# quadruped-robot.net
KiCad netlist of a schematic drawn in EAGLE
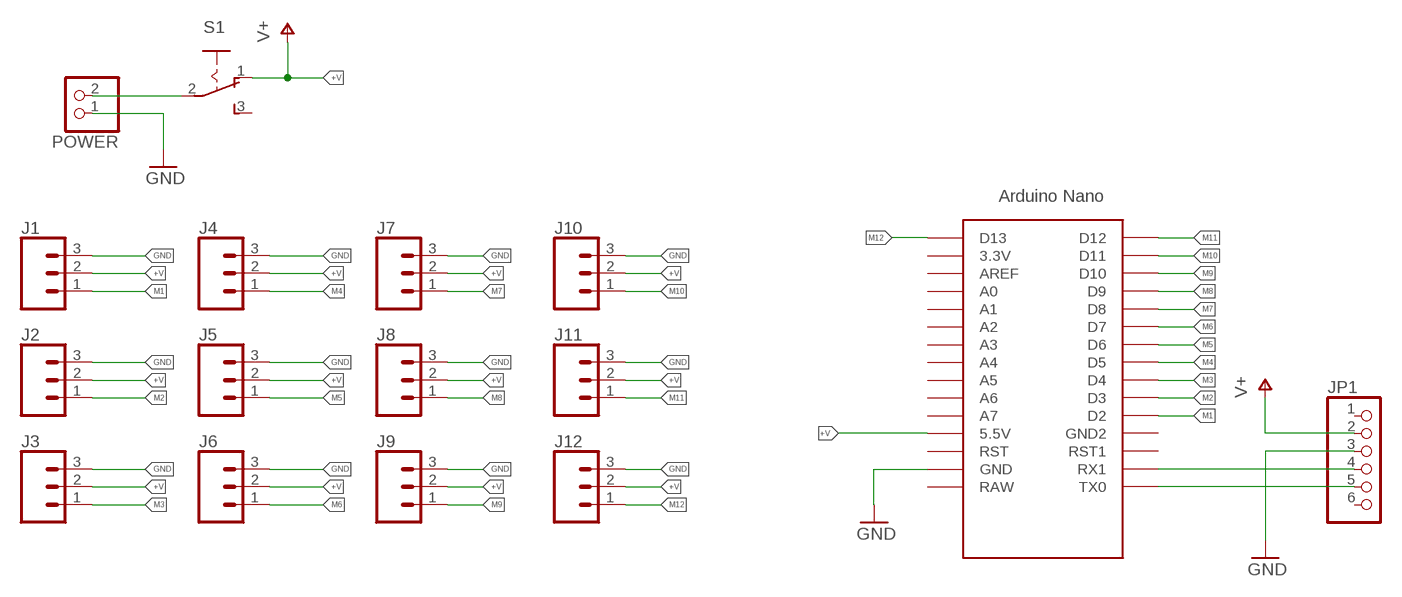
[diagram p0: schematic, sheet 1]

(export (version "E")
  (design (tool "Eeschema 10.0.6"))
  (components
    (comp (ref "J1")
      (value "CONN_03")
      (footprint "eagle-import:1X03")
      (libsource (lib "eagle-import") (part "CONN_03"))
    )
    (comp (ref "J2")
      (value "CONN_03")
      (footprint "eagle-import:1X03")
      (libsource (lib "eagle-import") (part "CONN_03"))
    )
    (comp (ref "J3")
      (value "CONN_03")
      (footprint "eagle-import:1X03")
      (libsource (lib "eagle-import") (part "CONN_03"))
    )
    (comp (ref "J4")
      (value "CONN_03")
      (footprint "eagle-import:1X03")
      (libsource (lib "eagle-import") (part "CONN_03"))
    )
    (comp (ref "J5")
      (value "CONN_03")
      (footprint "eagle-import:1X03")
      (libsource (lib "eagle-import") (part "CONN_03"))
    )
    (comp (ref "J6")
      (value "CONN_03")
      (footprint "eagle-import:1X03")
      (libsource (lib "eagle-import") (part "CONN_03"))
    )
    (comp (ref "J7")
      (value "CONN_03")
      (footprint "eagle-import:1X03")
      (libsource (lib "eagle-import") (part "CONN_03"))
    )
    (comp (ref "J8")
      (value "CONN_03")
      (footprint "eagle-import:1X03")
      (libsource (lib "eagle-import") (part "CONN_03"))
    )
    (comp (ref "J9")
      (value "CONN_03")
      (footprint "eagle-import:1X03")
      (libsource (lib "eagle-import") (part "CONN_03"))
    )
    (comp (ref "J10")
      (value "CONN_03")
      (footprint "eagle-import:1X03")
      (libsource (lib "eagle-import") (part "CONN_03"))
    )
    (comp (ref "J11")
      (value "CONN_03")
      (footprint "eagle-import:1X03")
      (libsource (lib "eagle-import") (part "CONN_03"))
    )
    (comp (ref "J12")
      (value "CONN_03")
      (footprint "eagle-import:1X03")
      (libsource (lib "eagle-import") (part "CONN_03"))
    )
    (comp (ref "JP1")
      (value "PINHD-1X6")
      (footprint "eagle-import:1X06")
      (libsource (lib "eagle-import") (part "PINHD-1X6"))
    )
    (comp (ref "POWER")
      (value "PINHD-1X2")
      (footprint "eagle-import:1X02")
      (libsource (lib "eagle-import") (part "PINHD-1X2"))
    )
    (comp (ref "S1")
      (value "255SB")
      (footprint "eagle-import:255SB")
      (libsource (lib "eagle-import") (part "255SB"))
    )
    (comp (ref "U$1")
      (value "NANO")
      (footprint "eagle-import:NANO")
      (libsource (lib "eagle-import") (part "NANO"))
    )
  )
  (nets
    (net (code "1") (name "+V") (class "Default")
      (node (ref "J1") (pin "2") (pinfunction "2_2") (pintype "passive"))
      (node (ref "J10") (pin "2") (pinfunction "2_2") (pintype "passive"))
      (node (ref "J11") (pin "2") (pinfunction "2_2") (pintype "passive"))
      (node (ref "J12") (pin "2") (pinfunction "2_2") (pintype "passive"))
      (node (ref "J2") (pin "2") (pinfunction "2_2") (pintype "passive"))
      (node (ref "J3") (pin "2") (pinfunction "2_2") (pintype "passive"))
      (node (ref "J4") (pin "2") (pinfunction "2_2") (pintype "passive"))
      (node (ref "J5") (pin "2") (pinfunction "2_2") (pintype "passive"))
      (node (ref "J6") (pin "2") (pinfunction "2_2") (pintype "passive"))
      (node (ref "J7") (pin "2") (pinfunction "2_2") (pintype "passive"))
      (node (ref "J8") (pin "2") (pinfunction "2_2") (pintype "passive"))
      (node (ref "J9") (pin "2") (pinfunction "2_2") (pintype "passive"))
      (node (ref "JP1") (pin "2") (pinfunction "2_2") (pintype "passive"))
      (node (ref "S1") (pin "1") (pinfunction "O_1") (pintype "passive"))
      (node (ref "U$1") (pin "5V") (pinfunction "5.5V_5V") (pintype "bidirectional"))
    )
    (net (code "2") (name "GND") (class "Default")
      (node (ref "J1") (pin "3") (pinfunction "3_3") (pintype "passive"))
      (node (ref "J10") (pin "3") (pinfunction "3_3") (pintype "passive"))
      (node (ref "J11") (pin "3") (pinfunction "3_3") (pintype "passive"))
      (node (ref "J12") (pin "3") (pinfunction "3_3") (pintype "passive"))
      (node (ref "J2") (pin "3") (pinfunction "3_3") (pintype "passive"))
      (node (ref "J3") (pin "3") (pinfunction "3_3") (pintype "passive"))
      (node (ref "J4") (pin "3") (pinfunction "3_3") (pintype "passive"))
      (node (ref "J5") (pin "3") (pinfunction "3_3") (pintype "passive"))
      (node (ref "J6") (pin "3") (pinfunction "3_3") (pintype "passive"))
      (node (ref "J7") (pin "3") (pinfunction "3_3") (pintype "passive"))
      (node (ref "J8") (pin "3") (pinfunction "3_3") (pintype "passive"))
      (node (ref "J9") (pin "3") (pinfunction "3_3") (pintype "passive"))
      (node (ref "JP1") (pin "3") (pinfunction "3_3") (pintype "passive"))
      (node (ref "POWER") (pin "1") (pinfunction "1_1") (pintype "passive"))
      (node (ref "U$1") (pin "GND") (pinfunction "GND_GND") (pintype "bidirectional"))
    )
    (net (code "3") (name "M1") (class "Default")
      (node (ref "J1") (pin "1") (pinfunction "1_1") (pintype "passive"))
      (node (ref "U$1") (pin "D2") (pinfunction "D2_D2") (pintype "bidirectional"))
    )
    (net (code "4") (name "M2") (class "Default")
      (node (ref "J2") (pin "1") (pinfunction "1_1") (pintype "passive"))
      (node (ref "U$1") (pin "D3") (pinfunction "D3_D3") (pintype "bidirectional"))
    )
    (net (code "5") (name "M3") (class "Default")
      (node (ref "J3") (pin "1") (pinfunction "1_1") (pintype "passive"))
      (node (ref "U$1") (pin "D4") (pinfunction "D4_D4") (pintype "bidirectional"))
    )
    (net (code "6") (name "M4") (class "Default")
      (node (ref "J4") (pin "1") (pinfunction "1_1") (pintype "passive"))
      (node (ref "U$1") (pin "D5") (pinfunction "D5_D5") (pintype "bidirectional"))
    )
    (net (code "7") (name "M5") (class "Default")
      (node (ref "J5") (pin "1") (pinfunction "1_1") (pintype "passive"))
      (node (ref "U$1") (pin "D6") (pinfunction "D6_D6") (pintype "bidirectional"))
    )
    (net (code "8") (name "M6") (class "Default")
      (node (ref "J6") (pin "1") (pinfunction "1_1") (pintype "passive"))
      (node (ref "U$1") (pin "D7") (pinfunction "D7_D7") (pintype "bidirectional"))
    )
    (net (code "9") (name "M7") (class "Default")
      (node (ref "J7") (pin "1") (pinfunction "1_1") (pintype "passive"))
      (node (ref "U$1") (pin "D8") (pinfunction "D8_D8") (pintype "bidirectional"))
    )
    (net (code "10") (name "M8") (class "Default")
      (node (ref "J8") (pin "1") (pinfunction "1_1") (pintype "passive"))
      (node (ref "U$1") (pin "D9") (pinfunction "D9_D9") (pintype "bidirectional"))
    )
    (net (code "11") (name "M9") (class "Default")
      (node (ref "J9") (pin "1") (pinfunction "1_1") (pintype "passive"))
      (node (ref "U$1") (pin "D10") (pinfunction "D10_D10") (pintype "bidirectional"))
    )
    (net (code "12") (name "M10") (class "Default")
      (node (ref "J10") (pin "1") (pinfunction "1_1") (pintype "passive"))
      (node (ref "U$1") (pin "D11") (pinfunction "D11_D11") (pintype "bidirectional"))
    )
    (net (code "13") (name "M11") (class "Default")
      (node (ref "J11") (pin "1") (pinfunction "1_1") (pintype "passive"))
      (node (ref "U$1") (pin "D12") (pinfunction "D12_D12") (pintype "bidirectional"))
    )
    (net (code "14") (name "M12") (class "Default")
      (node (ref "J12") (pin "1") (pinfunction "1_1") (pintype "passive"))
      (node (ref "U$1") (pin "D13") (pinfunction "D13_D13") (pintype "bidirectional"))
    )
    (net (code "15") (name "Net-(JP1-Pad4)") (class "Default")
      (node (ref "JP1") (pin "4") (pinfunction "4_4") (pintype "passive"))
      (node (ref "U$1") (pin "RX1") (pinfunction "RX1_RX1") (pintype "bidirectional"))
    )
    (net (code "16") (name "Net-(JP1-Pad5)") (class "Default")
      (node (ref "JP1") (pin "5") (pinfunction "5_5") (pintype "passive"))
      (node (ref "U$1") (pin "TX0") (pinfunction "TX0_TX0") (pintype "bidirectional"))
    )
    (net (code "17") (name "Net-(S1-P)") (class "Default")
      (node (ref "POWER") (pin "2") (pinfunction "2_2") (pintype "passive"))
      (node (ref "S1") (pin "2") (pinfunction "P_2") (pintype "passive"))
    )
    (net (code "18") (name "unconnected-(JP1-Pad1)") (class "Default")
      (node (ref "JP1") (pin "1") (pinfunction "1_1") (pintype "passive"))
    )
    (net (code "19") (name "unconnected-(JP1-Pad6)") (class "Default")
      (node (ref "JP1") (pin "6") (pinfunction "6_6") (pintype "passive"))
    )
    (net (code "20") (name "unconnected-(S1-S-Pad3)") (class "Default")
      (node (ref "S1") (pin "3") (pinfunction "S_3") (pintype "passive"))
    )
    (net (code "21") (name "unconnected-(U$1-GND2-PadGND1)") (class "Default")
      (node (ref "U$1") (pin "GND1") (pinfunction "GND2_GND1") (pintype "bidirectional"))
    )
    (net (code "22") (name "unconnected-(U$1-Pad3.3V)") (class "Default")
      (node (ref "U$1") (pin "3.3V") (pinfunction "3.3V_3.3V") (pintype "bidirectional"))
    )
    (net (code "23") (name "unconnected-(U$1-PadA0)") (class "Default")
      (node (ref "U$1") (pin "A0") (pinfunction "A0_A0") (pintype "bidirectional"))
    )
    (net (code "24") (name "unconnected-(U$1-PadA1)") (class "Default")
      (node (ref "U$1") (pin "A1") (pinfunction "A1_A1") (pintype "bidirectional"))
    )
    (net (code "25") (name "unconnected-(U$1-PadA2)") (class "Default")
      (node (ref "U$1") (pin "A2") (pinfunction "A2_A2") (pintype "bidirectional"))
    )
    (net (code "26") (name "unconnected-(U$1-PadA3)") (class "Default")
      (node (ref "U$1") (pin "A3") (pinfunction "A3_A3") (pintype "bidirectional"))
    )
    (net (code "27") (name "unconnected-(U$1-PadA4)") (class "Default")
      (node (ref "U$1") (pin "A4") (pinfunction "A4_A4") (pintype "bidirectional"))
    )
    (net (code "28") (name "unconnected-(U$1-PadA5)") (class "Default")
      (node (ref "U$1") (pin "A5") (pinfunction "A5_A5") (pintype "bidirectional"))
    )
    (net (code "29") (name "unconnected-(U$1-PadA6)") (class "Default")
      (node (ref "U$1") (pin "A6") (pinfunction "A6_A6") (pintype "bidirectional"))
    )
    (net (code "30") (name "unconnected-(U$1-PadA7)") (class "Default")
      (node (ref "U$1") (pin "A7") (pinfunction "A7_A7") (pintype "bidirectional"))
    )
    (net (code "31") (name "unconnected-(U$1-PadAREF)") (class "Default")
      (node (ref "U$1") (pin "AREF") (pinfunction "AREF_AREF") (pintype "bidirectional"))
    )
    (net (code "32") (name "unconnected-(U$1-PadICSP1)") (class "Default")
      (node (ref "U$1") (pin "ICSP1") (pinfunction "ICSP1_ICSP1") (pintype "bidirectional"))
    )
    (net (code "33") (name "unconnected-(U$1-PadICSP2)") (class "Default")
      (node (ref "U$1") (pin "ICSP2") (pinfunction "ICSP2_ICSP2") (pintype "bidirectional"))
    )
    (net (code "34") (name "unconnected-(U$1-PadICSP3)") (class "Default")
      (node (ref "U$1") (pin "ICSP3") (pinfunction "ICSP3_ICSP3") (pintype "bidirectional"))
    )
    (net (code "35") (name "unconnected-(U$1-PadICSP4)") (class "Default")
      (node (ref "U$1") (pin "ICSP4") (pinfunction "ICSP4_ICSP4") (pintype "bidirectional"))
    )
    (net (code "36") (name "unconnected-(U$1-PadICSP5)") (class "Default")
      (node (ref "U$1") (pin "ICSP5") (pinfunction "ICSP5_ICSP5") (pintype "bidirectional"))
    )
    (net (code "37") (name "unconnected-(U$1-PadICSP6)") (class "Default")
      (node (ref "U$1") (pin "ICSP6") (pinfunction "ICSP6_ICSP6") (pintype "bidirectional"))
    )
    (net (code "38") (name "unconnected-(U$1-PadRAW)") (class "Default")
      (node (ref "U$1") (pin "RAW") (pinfunction "RAW_RAW") (pintype "bidirectional"))
    )
    (net (code "39") (name "unconnected-(U$1-PadRST)") (class "Default")
      (node (ref "U$1") (pin "RST") (pinfunction "RST_RST") (pintype "bidirectional"))
    )
    (net (code "40") (name "unconnected-(U$1-PadRST1)") (class "Default")
      (node (ref "U$1") (pin "RST1") (pinfunction "RST1_RST1") (pintype "bidirectional"))
    )
  )
)
